# xyzzy_motor_controller_top_v1_0.net
KiCad netlist of a schematic drawn in EAGLE
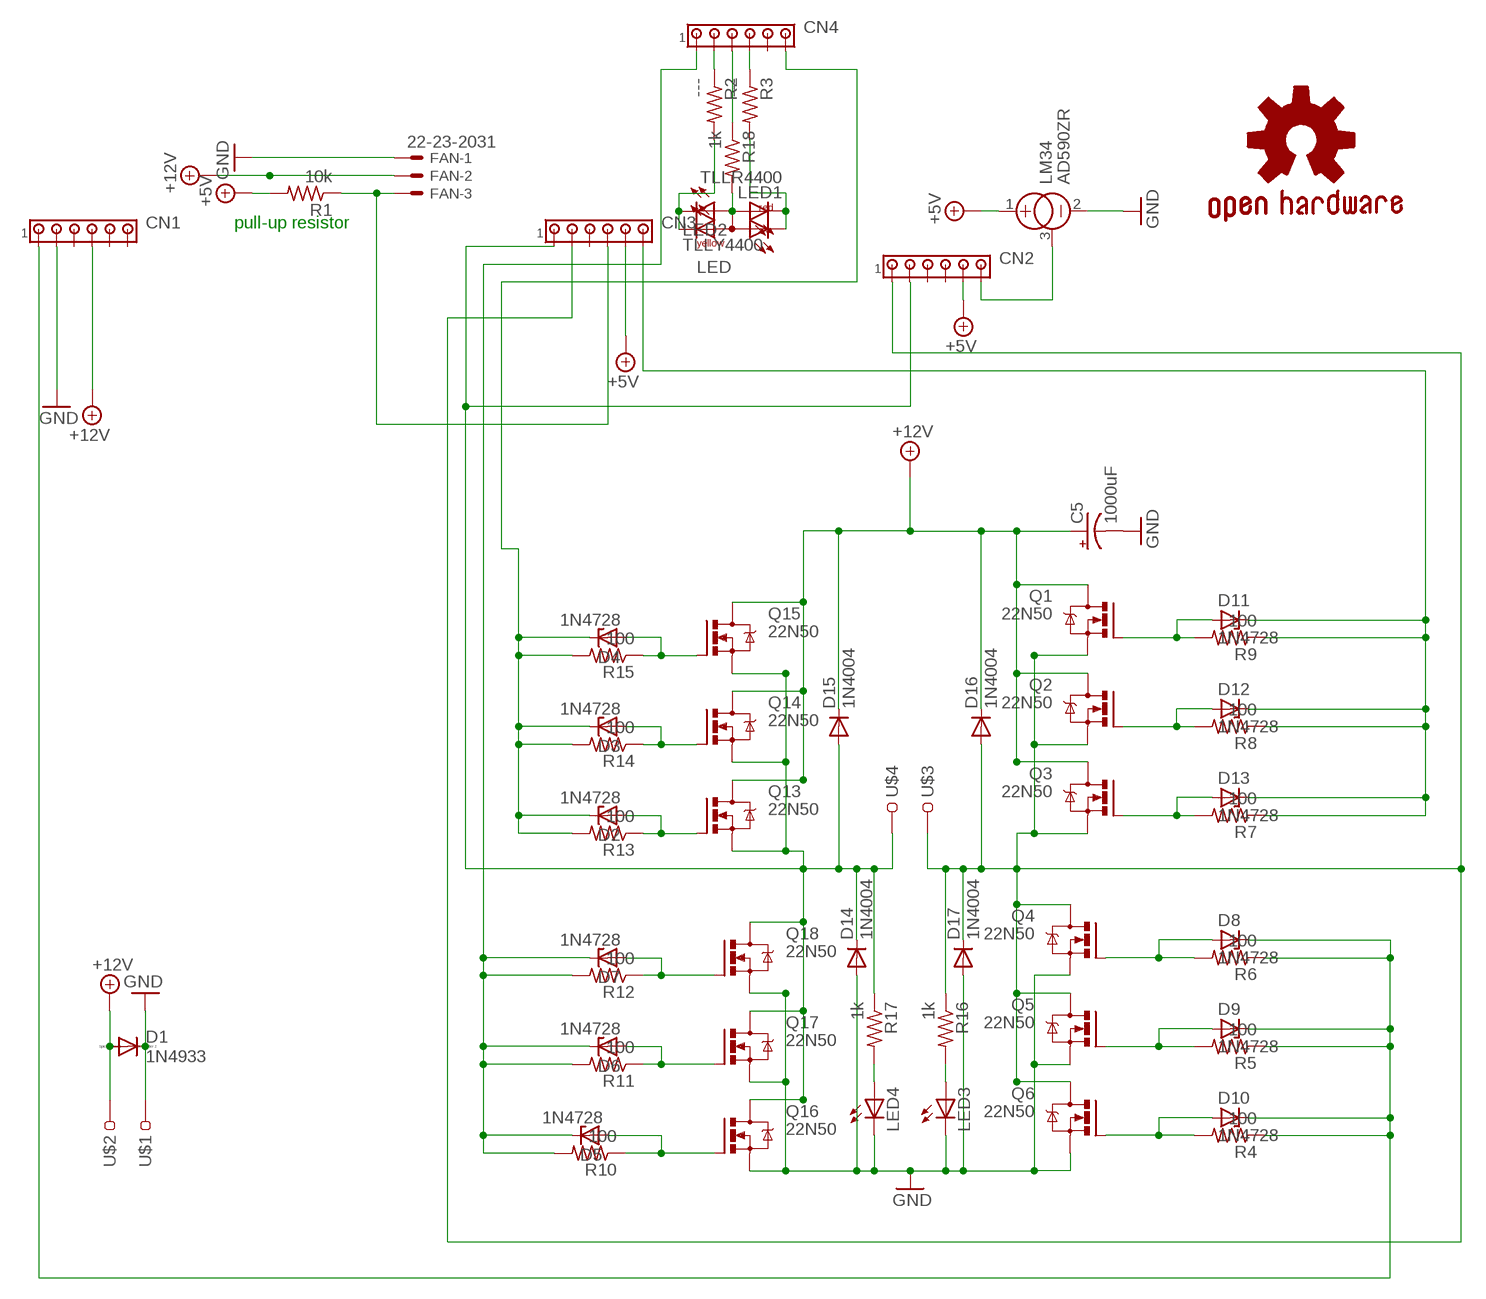
[diagram p0: schematic, sheet 1]

(export (version "E")
  (design (tool "Eeschema 10.0.6"))
  (components
    (comp (ref "C5")
      (value "1000uF")
      (footprint "eagle-import:E5-13")
      (libsource (lib "eagle-import") (part "CPOL-USE5-13"))
    )
    (comp (ref "CN1")
      (value "MTA06-100")
      (footprint "eagle-import:10X06MTA")
      (libsource (lib "eagle-import") (part "MTA06-100"))
    )
    (comp (ref "CN2")
      (value "MTA06-100")
      (footprint "eagle-import:10X06MTA")
      (libsource (lib "eagle-import") (part "MTA06-100"))
    )
    (comp (ref "CN3")
      (value "MTA06-100")
      (footprint "eagle-import:10X06MTA")
      (libsource (lib "eagle-import") (part "MTA06-100"))
    )
    (comp (ref "CN4")
      (value "MTA06-100")
      (footprint "eagle-import:10X06MTA")
      (libsource (lib "eagle-import") (part "MTA06-100"))
    )
    (comp (ref "D1")
      (value "1N4933")
      (footprint "eagle-import:DO41-10")
      (libsource (lib "eagle-import") (part "1N4933"))
    )
    (comp (ref "D2")
      (value "1N4728")
      (footprint "eagle-import:DO41Z10")
      (libsource (lib "eagle-import") (part "1N4728"))
    )
    (comp (ref "D3")
      (value "1N4728")
      (footprint "eagle-import:DO41Z10")
      (libsource (lib "eagle-import") (part "1N4728"))
    )
    (comp (ref "D4")
      (value "1N4728")
      (footprint "eagle-import:DO41Z10")
      (libsource (lib "eagle-import") (part "1N4728"))
    )
    (comp (ref "D5")
      (value "1N4728")
      (footprint "eagle-import:DO41Z10")
      (libsource (lib "eagle-import") (part "1N4728"))
    )
    (comp (ref "D6")
      (value "1N4728")
      (footprint "eagle-import:DO41Z10")
      (libsource (lib "eagle-import") (part "1N4728"))
    )
    (comp (ref "D7")
      (value "1N4728")
      (footprint "eagle-import:DO41Z10")
      (libsource (lib "eagle-import") (part "1N4728"))
    )
    (comp (ref "D8")
      (value "1N4728")
      (footprint "eagle-import:DO41Z10")
      (libsource (lib "eagle-import") (part "1N4728"))
    )
    (comp (ref "D9")
      (value "1N4728")
      (footprint "eagle-import:DO41Z10")
      (libsource (lib "eagle-import") (part "1N4728"))
    )
    (comp (ref "D10")
      (value "1N4728")
      (footprint "eagle-import:DO41Z10")
      (libsource (lib "eagle-import") (part "1N4728"))
    )
    (comp (ref "D11")
      (value "1N4728")
      (footprint "eagle-import:DO41Z10")
      (libsource (lib "eagle-import") (part "1N4728"))
    )
    (comp (ref "D12")
      (value "1N4728")
      (footprint "eagle-import:DO41Z10")
      (libsource (lib "eagle-import") (part "1N4728"))
    )
    (comp (ref "D13")
      (value "1N4728")
      (footprint "eagle-import:DO41Z10")
      (libsource (lib "eagle-import") (part "1N4728"))
    )
    (comp (ref "D14")
      (value "1N4004")
      (footprint "eagle-import:DO41-10")
      (libsource (lib "eagle-import") (part "1N4004"))
    )
    (comp (ref "D15")
      (value "1N4004")
      (footprint "eagle-import:DO41-10")
      (libsource (lib "eagle-import") (part "1N4004"))
    )
    (comp (ref "D16")
      (value "1N4004")
      (footprint "eagle-import:DO41-10")
      (libsource (lib "eagle-import") (part "1N4004"))
    )
    (comp (ref "D17")
      (value "1N4004")
      (footprint "eagle-import:DO41-10")
      (libsource (lib "eagle-import") (part "1N4004"))
    )
    (comp (ref "FAN")
      (value "22-23-2031")
      (footprint "eagle-import:22-23-2031")
      (fields (field (name "MF") "MOLEX"))
      (libsource (lib "eagle-import") (part "22-23-2031"))
    )
    (comp (ref "GOLD_ORB_SM2")
      (value "OSHWLOGO_GOLD_ORB_MED")
      (footprint "eagle-import:OSHW1")
      (libsource (lib "eagle-import") (part "OSHWLOGO_GOLD_ORB_MED"))
    )
    (comp (ref "LED")
      (value "DUOLED-RY-A")
      (footprint "eagle-import:DUOLED-A-5MM")
      (libsource (lib "eagle-import") (part "DUOLED-RY-A"))
    )
    (comp (ref "LED1")
      (value "TLLR4400")
      (footprint "eagle-import:LED3MM")
      (fields (field (name "MF") "VISHAY SEMICONDUCTOR"))
      (libsource (lib "eagle-import") (part "TLLR4400"))
    )
    (comp (ref "LED2")
      (value "TLLY4400")
      (footprint "eagle-import:LED3MM")
      (fields (field (name "MF") "VISHAY SEMICONDUCTOR"))
      (libsource (lib "eagle-import") (part "TLLY4400"))
    )
    (comp (ref "LED3")
      (value "LED3MM")
      (footprint "eagle-import:LED3MM")
      (libsource (lib "eagle-import") (part "LED3MM"))
    )
    (comp (ref "LED4")
      (value "LED3MM")
      (footprint "eagle-import:LED3MM")
      (libsource (lib "eagle-import") (part "LED3MM"))
    )
    (comp (ref "LM34")
      (value "AD590ZR")
      (footprint "eagle-import:TO92")
      (libsource (lib "eagle-import") (part "AD590ZR"))
    )
    (comp (ref "Q1")
      (value "22N50")
      (footprint "eagle-import:TO220BV")
      (libsource (lib "eagle-import") (part "IRF530"))
    )
    (comp (ref "Q2")
      (value "22N50")
      (footprint "eagle-import:TO220BV")
      (libsource (lib "eagle-import") (part "IRF530"))
    )
    (comp (ref "Q3")
      (value "22N50")
      (footprint "eagle-import:TO220BV")
      (libsource (lib "eagle-import") (part "IRF530"))
    )
    (comp (ref "Q4")
      (value "22N50")
      (footprint "eagle-import:TO220BV")
      (libsource (lib "eagle-import") (part "IRF530"))
    )
    (comp (ref "Q5")
      (value "22N50")
      (footprint "eagle-import:TO220BV")
      (libsource (lib "eagle-import") (part "IRF530"))
    )
    (comp (ref "Q6")
      (value "22N50")
      (footprint "eagle-import:TO220BV")
      (libsource (lib "eagle-import") (part "IRF530"))
    )
    (comp (ref "Q13")
      (value "22N50")
      (footprint "eagle-import:TO220BV")
      (libsource (lib "eagle-import") (part "IRF530"))
    )
    (comp (ref "Q14")
      (value "22N50")
      (footprint "eagle-import:TO220BV")
      (libsource (lib "eagle-import") (part "IRF530"))
    )
    (comp (ref "Q15")
      (value "22N50")
      (footprint "eagle-import:TO220BV")
      (libsource (lib "eagle-import") (part "IRF530"))
    )
    (comp (ref "Q16")
      (value "22N50")
      (footprint "eagle-import:TO220BV")
      (libsource (lib "eagle-import") (part "IRF530"))
    )
    (comp (ref "Q17")
      (value "22N50")
      (footprint "eagle-import:TO220BV")
      (libsource (lib "eagle-import") (part "IRF530"))
    )
    (comp (ref "Q18")
      (value "22N50")
      (footprint "eagle-import:TO220BV")
      (libsource (lib "eagle-import") (part "IRF530"))
    )
    (comp (ref "R1")
      (value "10k")
      (footprint "eagle-import:0207_12")
      (libsource (lib "eagle-import") (part "R-US_0207/12"))
    )
    (comp (ref "R2")
      (value "---")
      (footprint "eagle-import:0207_12")
      (libsource (lib "eagle-import") (part "R-US_0207/12"))
    )
    (comp (ref "R3")
      (value "---")
      (footprint "eagle-import:0207_12")
      (libsource (lib "eagle-import") (part "R-US_0207/12"))
    )
    (comp (ref "R4")
      (value "100")
      (footprint "eagle-import:0207_12")
      (libsource (lib "eagle-import") (part "R-US_0207/12"))
    )
    (comp (ref "R5")
      (value "100")
      (footprint "eagle-import:0207_12")
      (libsource (lib "eagle-import") (part "R-US_0207/12"))
    )
    (comp (ref "R6")
      (value "100")
      (footprint "eagle-import:0207_12")
      (libsource (lib "eagle-import") (part "R-US_0207/12"))
    )
    (comp (ref "R7")
      (value "100")
      (footprint "eagle-import:0207_12")
      (libsource (lib "eagle-import") (part "R-US_0207/12"))
    )
    (comp (ref "R8")
      (value "100")
      (footprint "eagle-import:0207_12")
      (libsource (lib "eagle-import") (part "R-US_0207/12"))
    )
    (comp (ref "R9")
      (value "100")
      (footprint "eagle-import:0207_12")
      (libsource (lib "eagle-import") (part "R-US_0207/12"))
    )
    (comp (ref "R10")
      (value "100")
      (footprint "eagle-import:0207_12")
      (libsource (lib "eagle-import") (part "R-US_0207/12"))
    )
    (comp (ref "R11")
      (value "100")
      (footprint "eagle-import:0207_12")
      (libsource (lib "eagle-import") (part "R-US_0207/12"))
    )
    (comp (ref "R12")
      (value "100")
      (footprint "eagle-import:0207_12")
      (libsource (lib "eagle-import") (part "R-US_0207/12"))
    )
    (comp (ref "R13")
      (value "100")
      (footprint "eagle-import:0207_12")
      (libsource (lib "eagle-import") (part "R-US_0207/12"))
    )
    (comp (ref "R14")
      (value "100")
      (footprint "eagle-import:0207_12")
      (libsource (lib "eagle-import") (part "R-US_0207/12"))
    )
    (comp (ref "R15")
      (value "100")
      (footprint "eagle-import:0207_12")
      (libsource (lib "eagle-import") (part "R-US_0207/12"))
    )
    (comp (ref "R16")
      (value "1k")
      (footprint "eagle-import:0207_12")
      (libsource (lib "eagle-import") (part "R-US_0207/12"))
    )
    (comp (ref "R17")
      (value "1k")
      (footprint "eagle-import:0207_12")
      (libsource (lib "eagle-import") (part "R-US_0207/12"))
    )
    (comp (ref "R18")
      (value "1k")
      (footprint "eagle-import:0207_12")
      (libsource (lib "eagle-import") (part "R-US_0207/12"))
    )
    (comp (ref "U$1")
      (value "TAB-CON")
      (footprint "eagle-import:SPADE")
      (libsource (lib "eagle-import") (part "TAB-CON"))
    )
    (comp (ref "U$2")
      (value "TAB-CON")
      (footprint "eagle-import:SPADE")
      (libsource (lib "eagle-import") (part "TAB-CON"))
    )
    (comp (ref "U$3")
      (value "TAB-CON")
      (footprint "eagle-import:SPADE")
      (libsource (lib "eagle-import") (part "TAB-CON"))
    )
    (comp (ref "U$4")
      (value "TAB-CON")
      (footprint "eagle-import:SPADE")
      (libsource (lib "eagle-import") (part "TAB-CON"))
    )
  )
  (nets
    (net (code "1") (name "+5V") (class "Default")
      (node (ref "CN2") (pin "5") (pinfunction "5_5") (pintype "passive"))
      (node (ref "CN3") (pin "5") (pinfunction "5_5") (pintype "passive"))
      (node (ref "LM34") (pin "1") (pinfunction "+_1") (pintype "input"))
      (node (ref "R1") (pin "2") (pinfunction "2_2") (pintype "passive"))
    )
    (net (code "2") (name "+12V") (class "Default")
      (node (ref "C5") (pin "+") (pinfunction "+_+") (pintype "passive"))
      (node (ref "CN1") (pin "4") (pinfunction "4_4") (pintype "passive"))
      (node (ref "D1") (pin "A") (pinfunction "A_A") (pintype "passive"))
      (node (ref "D15") (pin "C") (pinfunction "C_C") (pintype "passive"))
      (node (ref "D16") (pin "C") (pinfunction "C_C") (pintype "passive"))
      (node (ref "FAN") (pin "2") (pinfunction "S_2") (pintype "passive"))
      (node (ref "Q1") (pin "D") (pinfunction "D_D") (pintype "passive"))
      (node (ref "Q13") (pin "D") (pinfunction "D_D") (pintype "passive"))
      (node (ref "Q14") (pin "D") (pinfunction "D_D") (pintype "passive"))
      (node (ref "Q15") (pin "D") (pinfunction "D_D") (pintype "passive"))
      (node (ref "Q2") (pin "D") (pinfunction "D_D") (pintype "passive"))
      (node (ref "Q3") (pin "D") (pinfunction "D_D") (pintype "passive"))
      (node (ref "U$2") (pin "P$1") (pinfunction "1_P$1") (pintype "passive"))
      (node (ref "U$2") (pin "P$2") (pinfunction "1_P$2") (pintype "passive"))
    )
    (net (code "3") (name "GND") (class "Default")
      (node (ref "C5") (pin "-") (pinfunction "-_-") (pintype "passive"))
      (node (ref "CN1") (pin "2") (pinfunction "2_2") (pintype "passive"))
      (node (ref "D1") (pin "C") (pinfunction "C_C") (pintype "passive"))
      (node (ref "D14") (pin "A") (pinfunction "A_A") (pintype "passive"))
      (node (ref "D17") (pin "A") (pinfunction "A_A") (pintype "passive"))
      (node (ref "FAN") (pin "1") (pinfunction "S_1") (pintype "passive"))
      (node (ref "LED3") (pin "K") (pinfunction "C_K") (pintype "passive"))
      (node (ref "LED4") (pin "K") (pinfunction "C_K") (pintype "passive"))
      (node (ref "LM34") (pin "2") (pinfunction "-_2") (pintype "input"))
      (node (ref "Q16") (pin "S") (pinfunction "S_S") (pintype "passive"))
      (node (ref "Q17") (pin "S") (pinfunction "S_S") (pintype "passive"))
      (node (ref "Q18") (pin "S") (pinfunction "S_S") (pintype "passive"))
      (node (ref "Q4") (pin "S") (pinfunction "S_S") (pintype "passive"))
      (node (ref "Q5") (pin "S") (pinfunction "S_S") (pintype "passive"))
      (node (ref "Q6") (pin "S") (pinfunction "S_S") (pintype "passive"))
      (node (ref "U$1") (pin "P$1") (pinfunction "1_P$1") (pintype "passive"))
      (node (ref "U$1") (pin "P$2") (pinfunction "1_P$2") (pintype "passive"))
    )
    (net (code "4") (name "Net-(CN1-Pad1)") (class "Default")
      (node (ref "CN1") (pin "1") (pinfunction "1_1") (pintype "passive"))
      (node (ref "D10") (pin "C") (pinfunction "C_C") (pintype "passive"))
      (node (ref "D8") (pin "C") (pinfunction "C_C") (pintype "passive"))
      (node (ref "D9") (pin "C") (pinfunction "C_C") (pintype "passive"))
      (node (ref "R4") (pin "1") (pinfunction "1_1") (pintype "passive"))
      (node (ref "R5") (pin "1") (pinfunction "1_1") (pintype "passive"))
      (node (ref "R6") (pin "1") (pinfunction "1_1") (pintype "passive"))
    )
    (net (code "5") (name "Net-(CN2-Pad1)") (class "Default")
      (node (ref "CN2") (pin "1") (pinfunction "1_1") (pintype "passive"))
      (node (ref "CN3") (pin "2") (pinfunction "2_2") (pintype "passive"))
      (node (ref "D16") (pin "A") (pinfunction "A_A") (pintype "passive"))
      (node (ref "D17") (pin "C") (pinfunction "C_C") (pintype "passive"))
      (node (ref "Q1") (pin "S") (pinfunction "S_S") (pintype "passive"))
      (node (ref "Q2") (pin "S") (pinfunction "S_S") (pintype "passive"))
      (node (ref "Q3") (pin "S") (pinfunction "S_S") (pintype "passive"))
      (node (ref "Q4") (pin "D") (pinfunction "D_D") (pintype "passive"))
      (node (ref "Q5") (pin "D") (pinfunction "D_D") (pintype "passive"))
      (node (ref "Q6") (pin "D") (pinfunction "D_D") (pintype "passive"))
      (node (ref "R16") (pin "1") (pinfunction "1_1") (pintype "passive"))
      (node (ref "U$3") (pin "P$1") (pinfunction "1_P$1") (pintype "passive"))
      (node (ref "U$3") (pin "P$2") (pinfunction "1_P$2") (pintype "passive"))
    )
    (net (code "6") (name "Net-(CN2-Pad2)") (class "Default")
      (node (ref "CN2") (pin "2") (pinfunction "2_2") (pintype "passive"))
      (node (ref "CN3") (pin "1") (pinfunction "1_1") (pintype "passive"))
      (node (ref "D14") (pin "C") (pinfunction "C_C") (pintype "passive"))
      (node (ref "D15") (pin "A") (pinfunction "A_A") (pintype "passive"))
      (node (ref "Q13") (pin "S") (pinfunction "S_S") (pintype "passive"))
      (node (ref "Q14") (pin "S") (pinfunction "S_S") (pintype "passive"))
      (node (ref "Q15") (pin "S") (pinfunction "S_S") (pintype "passive"))
      (node (ref "Q16") (pin "D") (pinfunction "D_D") (pintype "passive"))
      (node (ref "Q17") (pin "D") (pinfunction "D_D") (pintype "passive"))
      (node (ref "Q18") (pin "D") (pinfunction "D_D") (pintype "passive"))
      (node (ref "R17") (pin "1") (pinfunction "1_1") (pintype "passive"))
      (node (ref "U$4") (pin "P$1") (pinfunction "1_P$1") (pintype "passive"))
      (node (ref "U$4") (pin "P$2") (pinfunction "1_P$2") (pintype "passive"))
    )
    (net (code "7") (name "Net-(CN3-Pad6)") (class "Default")
      (node (ref "CN3") (pin "6") (pinfunction "6_6") (pintype "passive"))
      (node (ref "D11") (pin "C") (pinfunction "C_C") (pintype "passive"))
      (node (ref "D12") (pin "C") (pinfunction "C_C") (pintype "passive"))
      (node (ref "D13") (pin "C") (pinfunction "C_C") (pintype "passive"))
      (node (ref "R7") (pin "1") (pinfunction "1_1") (pintype "passive"))
      (node (ref "R8") (pin "1") (pinfunction "1_1") (pintype "passive"))
      (node (ref "R9") (pin "1") (pinfunction "1_1") (pintype "passive"))
    )
    (net (code "8") (name "Net-(CN4-Pad1)") (class "Default")
      (node (ref "CN4") (pin "1") (pinfunction "1_1") (pintype "passive"))
      (node (ref "D5") (pin "C") (pinfunction "C_C") (pintype "passive"))
      (node (ref "D6") (pin "C") (pinfunction "C_C") (pintype "passive"))
      (node (ref "D7") (pin "C") (pinfunction "C_C") (pintype "passive"))
      (node (ref "R10") (pin "2") (pinfunction "2_2") (pintype "passive"))
      (node (ref "R11") (pin "2") (pinfunction "2_2") (pintype "passive"))
      (node (ref "R12") (pin "2") (pinfunction "2_2") (pintype "passive"))
    )
    (net (code "9") (name "Net-(CN4-Pad2)") (class "Default")
      (node (ref "CN4") (pin "2") (pinfunction "2_2") (pintype "passive"))
      (node (ref "R2") (pin "1") (pinfunction "1_1") (pintype "passive"))
    )
    (net (code "10") (name "Net-(CN4-Pad3)") (class "Default")
      (node (ref "CN4") (pin "3") (pinfunction "3_3") (pintype "passive"))
      (node (ref "R18") (pin "1") (pinfunction "1_1") (pintype "passive"))
    )
    (net (code "11") (name "Net-(CN4-Pad4)") (class "Default")
      (node (ref "CN4") (pin "4") (pinfunction "4_4") (pintype "passive"))
      (node (ref "R3") (pin "1") (pinfunction "1_1") (pintype "passive"))
    )
    (net (code "12") (name "Net-(CN4-Pad6)") (class "Default")
      (node (ref "CN4") (pin "6") (pinfunction "6_6") (pintype "passive"))
      (node (ref "D2") (pin "C") (pinfunction "C_C") (pintype "passive"))
      (node (ref "D3") (pin "C") (pinfunction "C_C") (pintype "passive"))
      (node (ref "D4") (pin "C") (pinfunction "C_C") (pintype "passive"))
      (node (ref "R13") (pin "2") (pinfunction "2_2") (pintype "passive"))
      (node (ref "R14") (pin "2") (pinfunction "2_2") (pintype "passive"))
      (node (ref "R15") (pin "2") (pinfunction "2_2") (pintype "passive"))
    )
    (net (code "13") (name "Net-(D2-PadA)") (class "Default")
      (node (ref "D2") (pin "A") (pinfunction "A_A") (pintype "passive"))
      (node (ref "Q13") (pin "G") (pinfunction "G_G") (pintype "passive"))
      (node (ref "R13") (pin "1") (pinfunction "1_1") (pintype "passive"))
    )
    (net (code "14") (name "Net-(D3-PadA)") (class "Default")
      (node (ref "D3") (pin "A") (pinfunction "A_A") (pintype "passive"))
      (node (ref "Q14") (pin "G") (pinfunction "G_G") (pintype "passive"))
      (node (ref "R14") (pin "1") (pinfunction "1_1") (pintype "passive"))
    )
    (net (code "15") (name "Net-(D4-PadA)") (class "Default")
      (node (ref "D4") (pin "A") (pinfunction "A_A") (pintype "passive"))
      (node (ref "Q15") (pin "G") (pinfunction "G_G") (pintype "passive"))
      (node (ref "R15") (pin "1") (pinfunction "1_1") (pintype "passive"))
    )
    (net (code "16") (name "Net-(D5-PadA)") (class "Default")
      (node (ref "D5") (pin "A") (pinfunction "A_A") (pintype "passive"))
      (node (ref "Q16") (pin "G") (pinfunction "G_G") (pintype "passive"))
      (node (ref "R10") (pin "1") (pinfunction "1_1") (pintype "passive"))
    )
    (net (code "17") (name "Net-(D6-PadA)") (class "Default")
      (node (ref "D6") (pin "A") (pinfunction "A_A") (pintype "passive"))
      (node (ref "Q17") (pin "G") (pinfunction "G_G") (pintype "passive"))
      (node (ref "R11") (pin "1") (pinfunction "1_1") (pintype "passive"))
    )
    (net (code "18") (name "Net-(D7-PadA)") (class "Default")
      (node (ref "D7") (pin "A") (pinfunction "A_A") (pintype "passive"))
      (node (ref "Q18") (pin "G") (pinfunction "G_G") (pintype "passive"))
      (node (ref "R12") (pin "1") (pinfunction "1_1") (pintype "passive"))
    )
    (net (code "19") (name "Net-(D8-PadA)") (class "Default")
      (node (ref "D8") (pin "A") (pinfunction "A_A") (pintype "passive"))
      (node (ref "Q4") (pin "G") (pinfunction "G_G") (pintype "passive"))
      (node (ref "R6") (pin "2") (pinfunction "2_2") (pintype "passive"))
    )
    (net (code "20") (name "Net-(D9-PadA)") (class "Default")
      (node (ref "D9") (pin "A") (pinfunction "A_A") (pintype "passive"))
      (node (ref "Q5") (pin "G") (pinfunction "G_G") (pintype "passive"))
      (node (ref "R5") (pin "2") (pinfunction "2_2") (pintype "passive"))
    )
    (net (code "21") (name "Net-(D10-PadA)") (class "Default")
      (node (ref "D10") (pin "A") (pinfunction "A_A") (pintype "passive"))
      (node (ref "Q6") (pin "G") (pinfunction "G_G") (pintype "passive"))
      (node (ref "R4") (pin "2") (pinfunction "2_2") (pintype "passive"))
    )
    (net (code "22") (name "Net-(D11-PadA)") (class "Default")
      (node (ref "D11") (pin "A") (pinfunction "A_A") (pintype "passive"))
      (node (ref "Q1") (pin "G") (pinfunction "G_G") (pintype "passive"))
      (node (ref "R9") (pin "2") (pinfunction "2_2") (pintype "passive"))
    )
    (net (code "23") (name "Net-(D12-PadA)") (class "Default")
      (node (ref "D12") (pin "A") (pinfunction "A_A") (pintype "passive"))
      (node (ref "Q2") (pin "G") (pinfunction "G_G") (pintype "passive"))
      (node (ref "R8") (pin "2") (pinfunction "2_2") (pintype "passive"))
    )
    (net (code "24") (name "Net-(D13-PadA)") (class "Default")
      (node (ref "D13") (pin "A") (pinfunction "A_A") (pintype "passive"))
      (node (ref "Q3") (pin "G") (pinfunction "G_G") (pintype "passive"))
      (node (ref "R7") (pin "2") (pinfunction "2_2") (pintype "passive"))
    )
    (net (code "25") (name "Net-(FANC-S)") (class "Default")
      (node (ref "CN3") (pin "4") (pinfunction "4_4") (pintype "passive"))
      (node (ref "FAN") (pin "3") (pinfunction "S_3") (pintype "passive"))
      (node (ref "R1") (pin "1") (pinfunction "1_1") (pintype "passive"))
    )
    (net (code "26") (name "Net-(LED-CY)") (class "Default")
      (node (ref "LED") (pin "CX") (pinfunction "CY_CX") (pintype "passive"))
      (node (ref "LED2") (pin "K") (pinfunction "C_K") (pintype "passive"))
      (node (ref "R2") (pin "2") (pinfunction "2_2") (pintype "passive"))
    )
    (net (code "27") (name "Net-(LED-PadA)") (class "Default")
      (node (ref "LED") (pin "A") (pinfunction "A_A") (pintype "passive"))
      (node (ref "LED1") (pin "A") (pinfunction "A_A") (pintype "passive"))
      (node (ref "LED2") (pin "A") (pinfunction "A_A") (pintype "passive"))
      (node (ref "R18") (pin "2") (pinfunction "2_2") (pintype "passive"))
    )
    (net (code "28") (name "Net-(LED1-C)") (class "Default")
      (node (ref "LED") (pin "CR") (pinfunction "CR_CR") (pintype "passive"))
      (node (ref "LED1") (pin "K") (pinfunction "C_K") (pintype "passive"))
      (node (ref "R3") (pin "2") (pinfunction "2_2") (pintype "passive"))
    )
    (net (code "29") (name "Net-(LED3-PadA)") (class "Default")
      (node (ref "LED3") (pin "A") (pinfunction "A_A") (pintype "passive"))
      (node (ref "R16") (pin "2") (pinfunction "2_2") (pintype "passive"))
    )
    (net (code "30") (name "Net-(LED4-PadA)") (class "Default")
      (node (ref "LED4") (pin "A") (pinfunction "A_A") (pintype "passive"))
      (node (ref "R17") (pin "2") (pinfunction "2_2") (pintype "passive"))
    )
    (net (code "31") (name "Net-(LM34-CAN)") (class "Default")
      (node (ref "CN2") (pin "6") (pinfunction "6_6") (pintype "passive"))
      (node (ref "LM34") (pin "3") (pinfunction "CAN_3") (pintype "passive"))
    )
    (net (code "32") (name "unconnected-(CN1-Pad3)") (class "Default")
      (node (ref "CN1") (pin "3") (pinfunction "3_3") (pintype "passive"))
    )
    (net (code "33") (name "unconnected-(CN1-Pad5)") (class "Default")
      (node (ref "CN1") (pin "5") (pinfunction "5_5") (pintype "passive"))
    )
    (net (code "34") (name "unconnected-(CN1-Pad6)") (class "Default")
      (node (ref "CN1") (pin "6") (pinfunction "6_6") (pintype "passive"))
    )
    (net (code "35") (name "unconnected-(CN2-Pad3)") (class "Default")
      (node (ref "CN2") (pin "3") (pinfunction "3_3") (pintype "passive"))
    )
    (net (code "36") (name "unconnected-(CN2-Pad4)") (class "Default")
      (node (ref "CN2") (pin "4") (pinfunction "4_4") (pintype "passive"))
    )
    (net (code "37") (name "unconnected-(CN3-Pad3)") (class "Default")
      (node (ref "CN3") (pin "3") (pinfunction "3_3") (pintype "passive"))
    )
    (net (code "38") (name "unconnected-(CN4-Pad5)") (class "Default")
      (node (ref "CN4") (pin "5") (pinfunction "5_5") (pintype "passive"))
    )
  )
)
